# SD_Share.net
KiCad netlist of a schematic drawn in Altium Designer
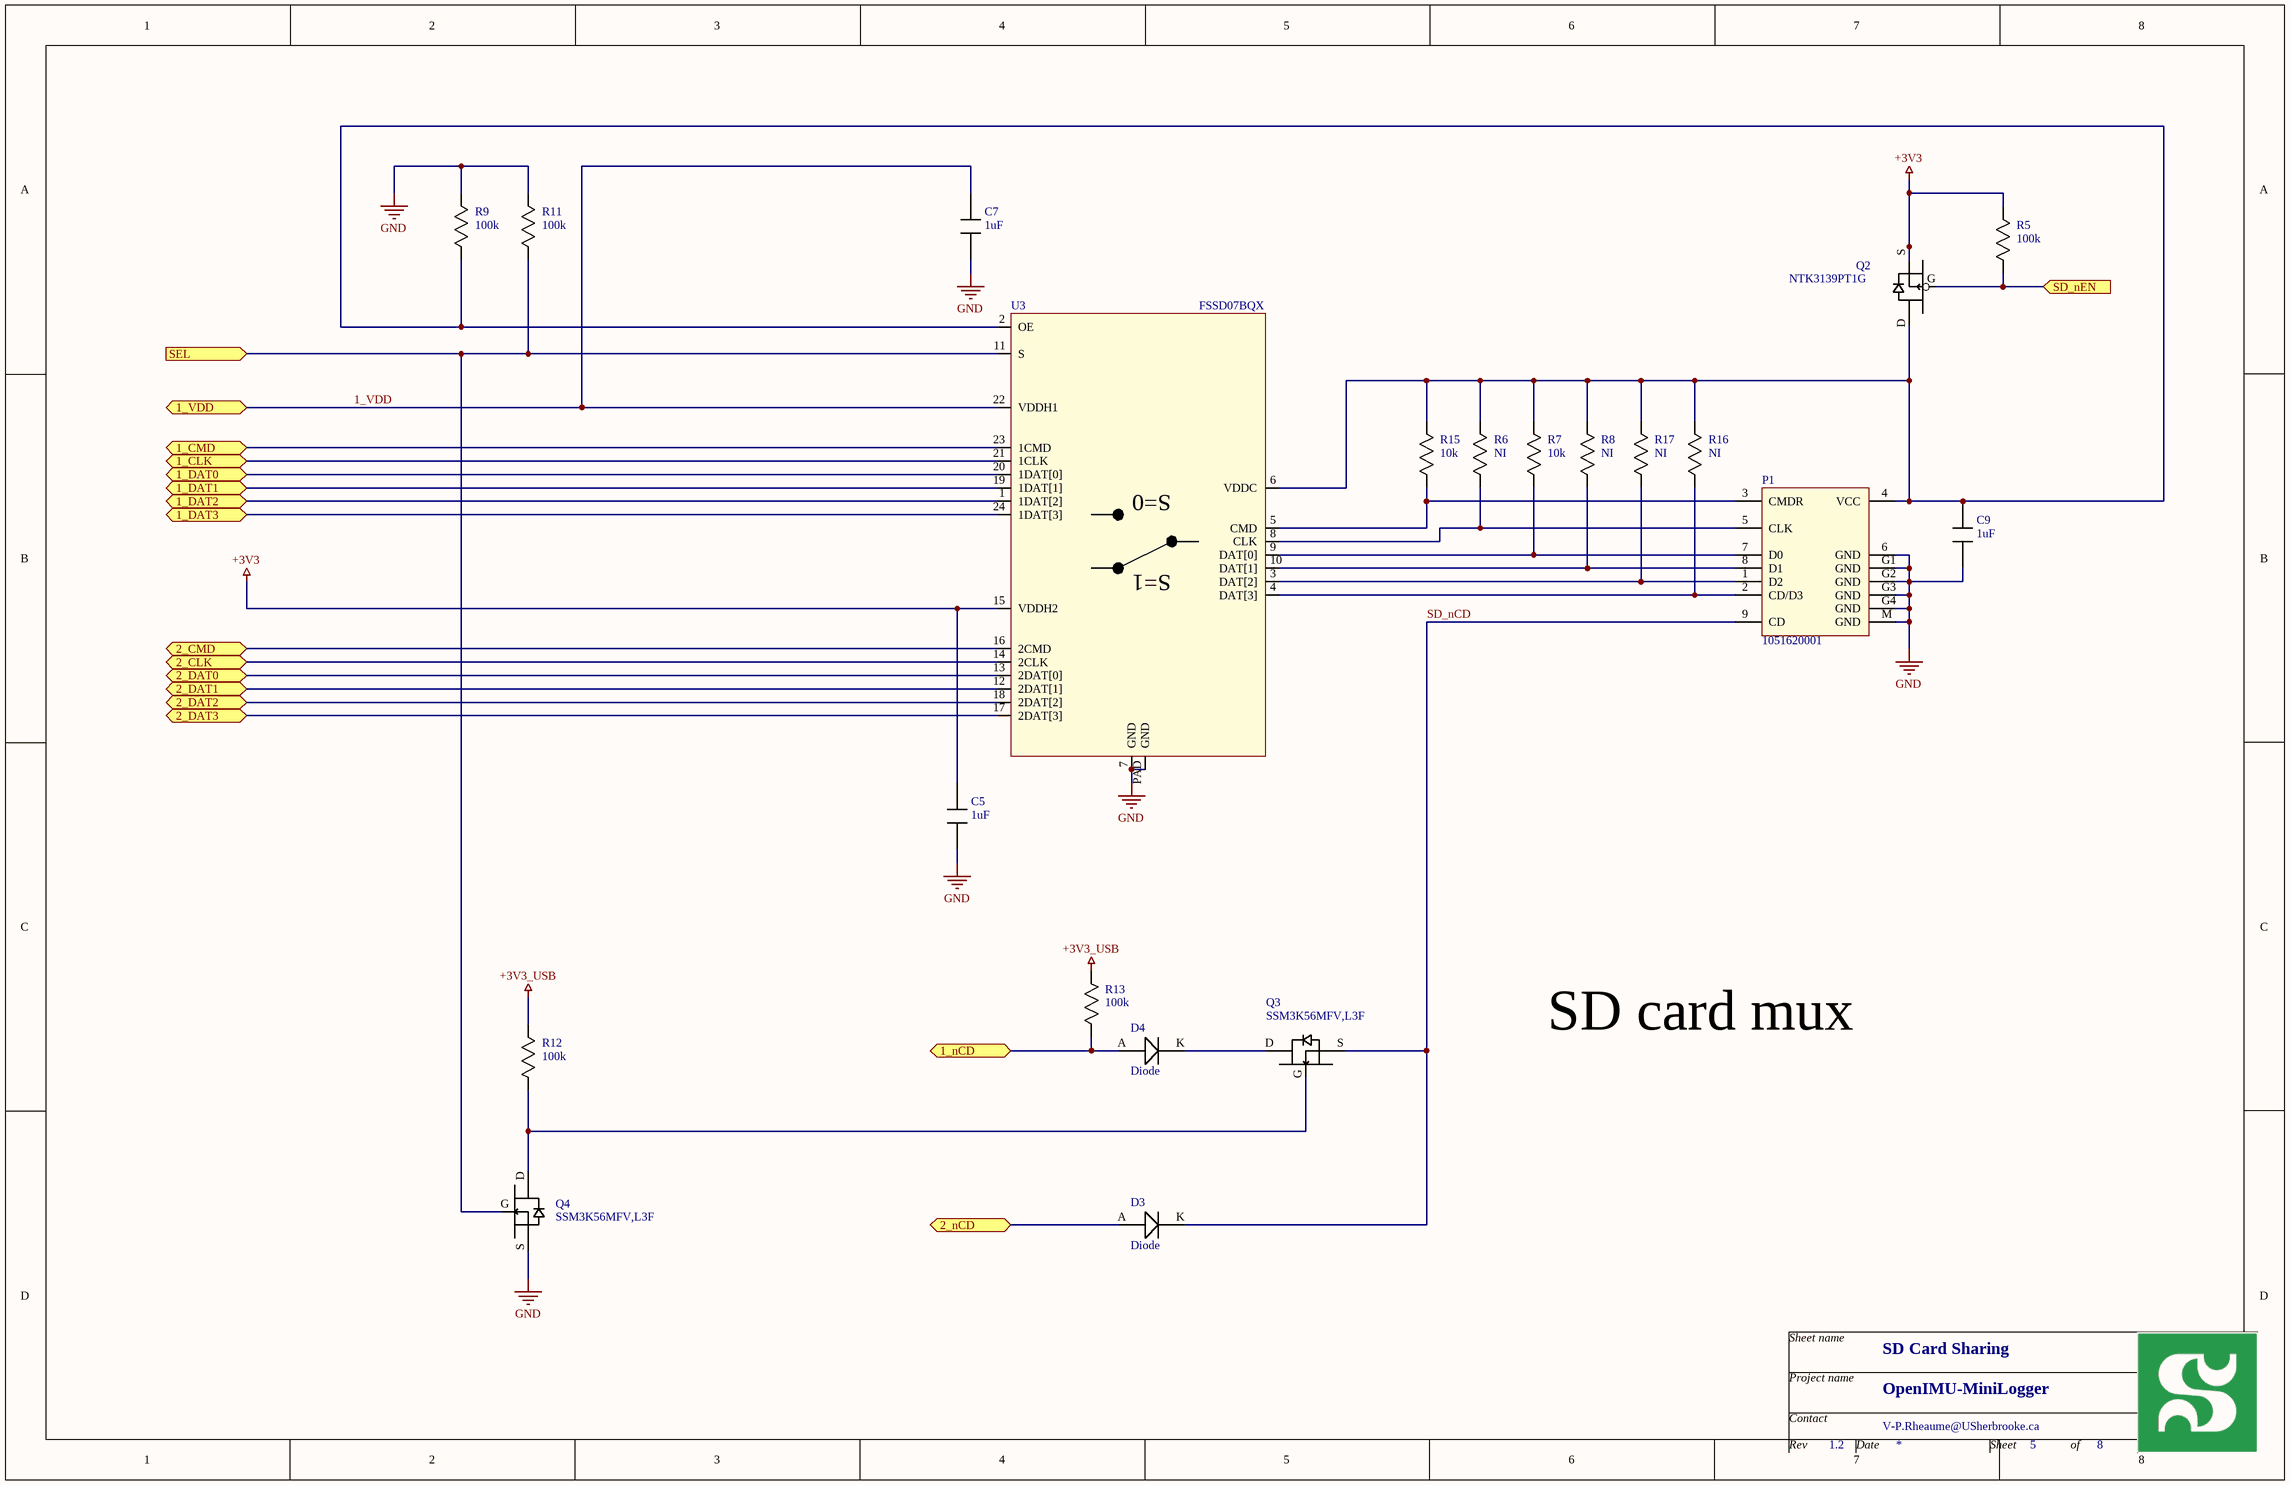
[diagram p0: SD_Share.SchDoc]

(export (version "E")
  (design (tool "Eeschema 10.0.6"))
  (components
    (comp (ref "C5")
      (value "1uF")
      (footprint "0603")
      (description "Capacitor")
      (fields (field (name "MFG") "Samsung"))
      (libsource (lib "INTER_2014") (part "Capacitor"))
    )
    (comp (ref "C7")
      (value "1uF")
      (footprint "0603")
      (description "Capacitor")
      (fields (field (name "MFG") "Samsung"))
      (libsource (lib "INTER_2014") (part "Capacitor"))
    )
    (comp (ref "C9")
      (value "1uF")
      (footprint "0603")
      (description "Capacitor")
      (fields (field (name "MFG") "Samsung"))
      (libsource (lib "INTER_2014") (part "Capacitor"))
    )
    (comp (ref "D3")
      (value "Diode")
      (footprint "DIODE_SOD523")
      (fields (field (name "MFG") "MCC"))
      (libsource (lib "INTER_2014") (part "Diode"))
    )
    (comp (ref "D4")
      (value "Diode")
      (footprint "DIODE_SOD523")
      (fields (field (name "MFG") "MCC"))
      (libsource (lib "INTER_2014") (part "Diode"))
    )
    (comp (ref "P1")
      (value "CON_uSD_1051620001")
      (footprint "CONN_uSD_MOLEX_1051620001")
      (description "Micro-SD card slot")
      (fields (field (name "MFG") "Molex") (field (name "MFG_PN") "1051620001"))
      (libsource (lib "INTER_2014") (part "CON_uSD_1051620001"))
    )
    (comp (ref "Q2")
      (value "MOSFET_P_GDS")
      (footprint "SOT723")
      (description "PMOS")
      (fields (field (name "MFG") "OnSemi") (field (name "MFG_PN") "NTK3139PT1G"))
      (libsource (lib "INTER_2014") (part "MOSFET_P_GDS"))
    )
    (comp (ref "Q3")
      (value "MOSFET_N_GDS")
      (footprint "SOT723")
      (description "NMOS")
      (fields (field (name "MFG") "Toshiba") (field (name "MFG_PN") "SSM3K56MFV,L3F"))
      (libsource (lib "INTER_2014") (part "MOSFET_N_GDS"))
    )
    (comp (ref "Q4")
      (value "MOSFET_N_GDS")
      (footprint "SOT723")
      (description "NMOS")
      (fields (field (name "MFG") "Toshiba") (field (name "MFG_PN") "SSM3K56MFV,L3F"))
      (libsource (lib "INTER_2014") (part "MOSFET_N_GDS"))
    )
    (comp (ref "R5")
      (value "100k")
      (footprint "0402")
      (description "Resistor")
      (fields (field (name "MFG") "Yageo"))
      (libsource (lib "INTER_2014") (part "Resistor"))
    )
    (comp (ref "R6")
      (value "Resistor")
      (footprint "0402")
      (fields (field (name "MFG") "Yageo") (field (name "NI") "NI"))
      (libsource (lib "INTER_2014") (part "Resistor"))
    )
    (comp (ref "R7")
      (value "10k")
      (footprint "0402")
      (description "Resistor")
      (fields (field (name "MFG") "Yageo"))
      (libsource (lib "INTER_2014") (part "Resistor"))
    )
    (comp (ref "R8")
      (value "Resistor")
      (footprint "0402")
      (fields (field (name "MFG") "Yageo") (field (name "NI") "NI"))
      (libsource (lib "INTER_2014") (part "Resistor"))
    )
    (comp (ref "R9")
      (value "100k")
      (footprint "0402")
      (description "Resistor")
      (fields (field (name "MFG") "Yageo"))
      (libsource (lib "INTER_2014") (part "Resistor"))
    )
    (comp (ref "R11")
      (value "100k")
      (footprint "0402")
      (description "Resistor")
      (fields (field (name "MFG") "Yageo"))
      (libsource (lib "INTER_2014") (part "Resistor"))
    )
    (comp (ref "R12")
      (value "100k")
      (footprint "0402")
      (description "Resistor")
      (fields (field (name "MFG") "Yageo"))
      (libsource (lib "INTER_2014") (part "Resistor"))
    )
    (comp (ref "R13")
      (value "100k")
      (footprint "0402")
      (description "Resistor")
      (fields (field (name "MFG") "Yageo"))
      (libsource (lib "INTER_2014") (part "Resistor"))
    )
    (comp (ref "R15")
      (value "10k")
      (footprint "0402")
      (description "Resistor")
      (fields (field (name "MFG") "Yageo"))
      (libsource (lib "INTER_2014") (part "Resistor"))
    )
    (comp (ref "R16")
      (value "Resistor")
      (footprint "0402")
      (fields (field (name "MFG") "Yageo") (field (name "NI") "NI"))
      (libsource (lib "INTER_2014") (part "Resistor"))
    )
    (comp (ref "R17")
      (value "Resistor")
      (footprint "0402")
      (fields (field (name "MFG") "Yageo") (field (name "NI") "NI"))
      (libsource (lib "INTER_2014") (part "Resistor"))
    )
    (comp (ref "U3")
      (value "FSSD07BQX")
      (footprint "MLP24")
      (description "SD Card Host multiplexer")
      (fields (field (name "MFG") "OnSemi") (field (name "MFG_PN") "FSSD07BQX"))
      (libsource (lib "INTER_2014") (part "FSSD07BQX"))
    )
  )
  (nets
    (net (code "1") (name "+3V3") (class "Default")
      (node (ref "C5") (pin "1") (pintype "passive"))
      (node (ref "Q2") (pin "S") (pintype "passive"))
      (node (ref "R5") (pin "1") (pintype "passive"))
      (node (ref "U3") (pin "15") (pinfunction "VDDH2_15") (pintype "passive"))
    )
    (net (code "2") (name "+3V3_USB") (class "Default")
      (node (ref "R12") (pin "1") (pintype "passive"))
      (node (ref "R13") (pin "1") (pintype "passive"))
    )
    (net (code "3") (name "/1_CLK") (class "Default")
      (node (ref "U3") (pin "21") (pinfunction "1CLK_21") (pintype "passive"))
    )
    (net (code "4") (name "/1_CMD") (class "Default")
      (node (ref "U3") (pin "23") (pinfunction "1CMD_23") (pintype "passive"))
    )
    (net (code "5") (name "/1_DAT0") (class "Default")
      (node (ref "U3") (pin "20") (pinfunction "1DAT[0]_20") (pintype "passive"))
    )
    (net (code "6") (name "/1_DAT1") (class "Default")
      (node (ref "U3") (pin "19") (pinfunction "1DAT[1]_19") (pintype "passive"))
    )
    (net (code "7") (name "/1_DAT2") (class "Default")
      (node (ref "U3") (pin "1") (pinfunction "1DAT[2]_1") (pintype "passive"))
    )
    (net (code "8") (name "/1_DAT3") (class "Default")
      (node (ref "U3") (pin "24") (pinfunction "1DAT[3]_24") (pintype "passive"))
    )
    (net (code "9") (name "/1_VDD") (class "Default")
      (node (ref "C7") (pin "1") (pintype "passive"))
      (node (ref "U3") (pin "22") (pinfunction "VDDH1_22") (pintype "passive"))
    )
    (net (code "10") (name "/1_nCD") (class "Default")
      (node (ref "D4") (pin "A") (pintype "passive"))
      (node (ref "R13") (pin "2") (pintype "passive"))
    )
    (net (code "11") (name "/2_CLK") (class "Default")
      (node (ref "U3") (pin "14") (pinfunction "2CLK_14") (pintype "passive"))
    )
    (net (code "12") (name "/2_CMD") (class "Default")
      (node (ref "U3") (pin "16") (pinfunction "2CMD_16") (pintype "passive"))
    )
    (net (code "13") (name "/2_DAT0") (class "Default")
      (node (ref "U3") (pin "13") (pinfunction "2DAT[0]_13") (pintype "passive"))
    )
    (net (code "14") (name "/2_DAT1") (class "Default")
      (node (ref "U3") (pin "12") (pinfunction "2DAT[1]_12") (pintype "passive"))
    )
    (net (code "15") (name "/2_DAT2") (class "Default")
      (node (ref "U3") (pin "18") (pinfunction "2DAT[2]_18") (pintype "passive"))
    )
    (net (code "16") (name "/2_DAT3") (class "Default")
      (node (ref "U3") (pin "17") (pinfunction "2DAT[3]_17") (pintype "passive"))
    )
    (net (code "17") (name "/2_nCD") (class "Default") (node (ref "D3") (pin "A") (pintype "passive")))
    (net (code "18") (name "/SD_nCD") (class "Default")
      (node (ref "D3") (pin "K") (pintype "passive"))
      (node (ref "P1") (pin "9") (pinfunction "CD_9") (pintype "passive"))
      (node (ref "Q3") (pin "S") (pintype "passive"))
    )
    (net (code "19") (name "/SD_nEN") (class "Default")
      (node (ref "Q2") (pin "G") (pintype "passive"))
      (node (ref "R5") (pin "2") (pintype "passive"))
    )
    (net (code "20") (name "/SEL") (class "Default")
      (node (ref "Q4") (pin "G") (pintype "passive"))
      (node (ref "R11") (pin "2") (pintype "passive"))
      (node (ref "U3") (pin "11") (pinfunction "S_11") (pintype "passive"))
    )
    (net (code "21") (name "GND") (class "Default")
      (node (ref "C5") (pin "2") (pintype "passive"))
      (node (ref "C7") (pin "2") (pintype "passive"))
      (node (ref "C9") (pin "2") (pintype "passive"))
      (node (ref "P1") (pin "6") (pinfunction "GND_6") (pintype "passive"))
      (node (ref "P1") (pin "G1") (pinfunction "GND_G1") (pintype "passive"))
      (node (ref "P1") (pin "G2") (pinfunction "GND_G2") (pintype "passive"))
      (node (ref "P1") (pin "G3") (pinfunction "GND_G3") (pintype "passive"))
      (node (ref "P1") (pin "G4") (pinfunction "GND_G4") (pintype "passive"))
      (node (ref "P1") (pin "M") (pinfunction "GND_M") (pintype "passive"))
      (node (ref "Q4") (pin "S") (pintype "passive"))
      (node (ref "R11") (pin "1") (pintype "passive"))
      (node (ref "R9") (pin "1") (pintype "passive"))
      (node (ref "U3") (pin "7") (pinfunction "GND_7") (pintype "passive"))
      (node (ref "U3") (pin "PAD") (pinfunction "GND_PAD") (pintype "passive"))
    )
    (net (code "22") (name "Net-(D4-PadK)") (class "Default")
      (node (ref "D4") (pin "K") (pintype "passive"))
      (node (ref "Q3") (pin "D") (pintype "passive"))
    )
    (net (code "23") (name "Net-(P1-CD{slash}D3)") (class "Default")
      (node (ref "P1") (pin "2") (pinfunction "CD/D3_2") (pintype "passive"))
      (node (ref "R16") (pin "2") (pintype "passive"))
      (node (ref "U3") (pin "4") (pinfunction "DAT[3]_4") (pintype "passive"))
    )
    (net (code "24") (name "Net-(P1-CLK)") (class "Default")
      (node (ref "P1") (pin "5") (pinfunction "CLK_5") (pintype "passive"))
      (node (ref "R6") (pin "2") (pintype "passive"))
      (node (ref "U3") (pin "8") (pinfunction "CLK_8") (pintype "passive"))
    )
    (net (code "25") (name "Net-(P1-CMDR)") (class "Default")
      (node (ref "P1") (pin "3") (pinfunction "CMDR_3") (pintype "passive"))
      (node (ref "R15") (pin "2") (pintype "passive"))
      (node (ref "U3") (pin "5") (pinfunction "CMD_5") (pintype "passive"))
    )
    (net (code "26") (name "Net-(P1-D0)") (class "Default")
      (node (ref "P1") (pin "7") (pinfunction "D0_7") (pintype "passive"))
      (node (ref "R7") (pin "2") (pintype "passive"))
      (node (ref "U3") (pin "9") (pinfunction "DAT[0]_9") (pintype "passive"))
    )
    (net (code "27") (name "Net-(P1-D1)") (class "Default")
      (node (ref "P1") (pin "8") (pinfunction "D1_8") (pintype "passive"))
      (node (ref "R8") (pin "2") (pintype "passive"))
      (node (ref "U3") (pin "10") (pinfunction "DAT[1]_10") (pintype "passive"))
    )
    (net (code "28") (name "Net-(P1-D2)") (class "Default")
      (node (ref "P1") (pin "1") (pinfunction "D2_1") (pintype "passive"))
      (node (ref "R17") (pin "2") (pintype "passive"))
      (node (ref "U3") (pin "3") (pinfunction "DAT[2]_3") (pintype "passive"))
    )
    (net (code "29") (name "Net-(P1-VCC)") (class "Default")
      (node (ref "C9") (pin "1") (pintype "passive"))
      (node (ref "P1") (pin "4") (pinfunction "VCC_4") (pintype "passive"))
      (node (ref "Q2") (pin "D") (pintype "passive"))
      (node (ref "R15") (pin "1") (pintype "passive"))
      (node (ref "R16") (pin "1") (pintype "passive"))
      (node (ref "R17") (pin "1") (pintype "passive"))
      (node (ref "R6") (pin "1") (pintype "passive"))
      (node (ref "R7") (pin "1") (pintype "passive"))
      (node (ref "R8") (pin "1") (pintype "passive"))
      (node (ref "R9") (pin "2") (pintype "passive"))
      (node (ref "U3") (pin "2") (pinfunction "OE_2") (pintype "passive"))
      (node (ref "U3") (pin "6") (pinfunction "VDDC_6") (pintype "passive"))
    )
    (net (code "30") (name "Net-(Q3-PadG)") (class "Default")
      (node (ref "Q3") (pin "G") (pintype "passive"))
      (node (ref "Q4") (pin "D") (pintype "passive"))
      (node (ref "R12") (pin "2") (pintype "passive"))
    )
  )
)
